# CM6206_PINOUT.net
KiCad netlist of a schematic drawn in Altium Designer
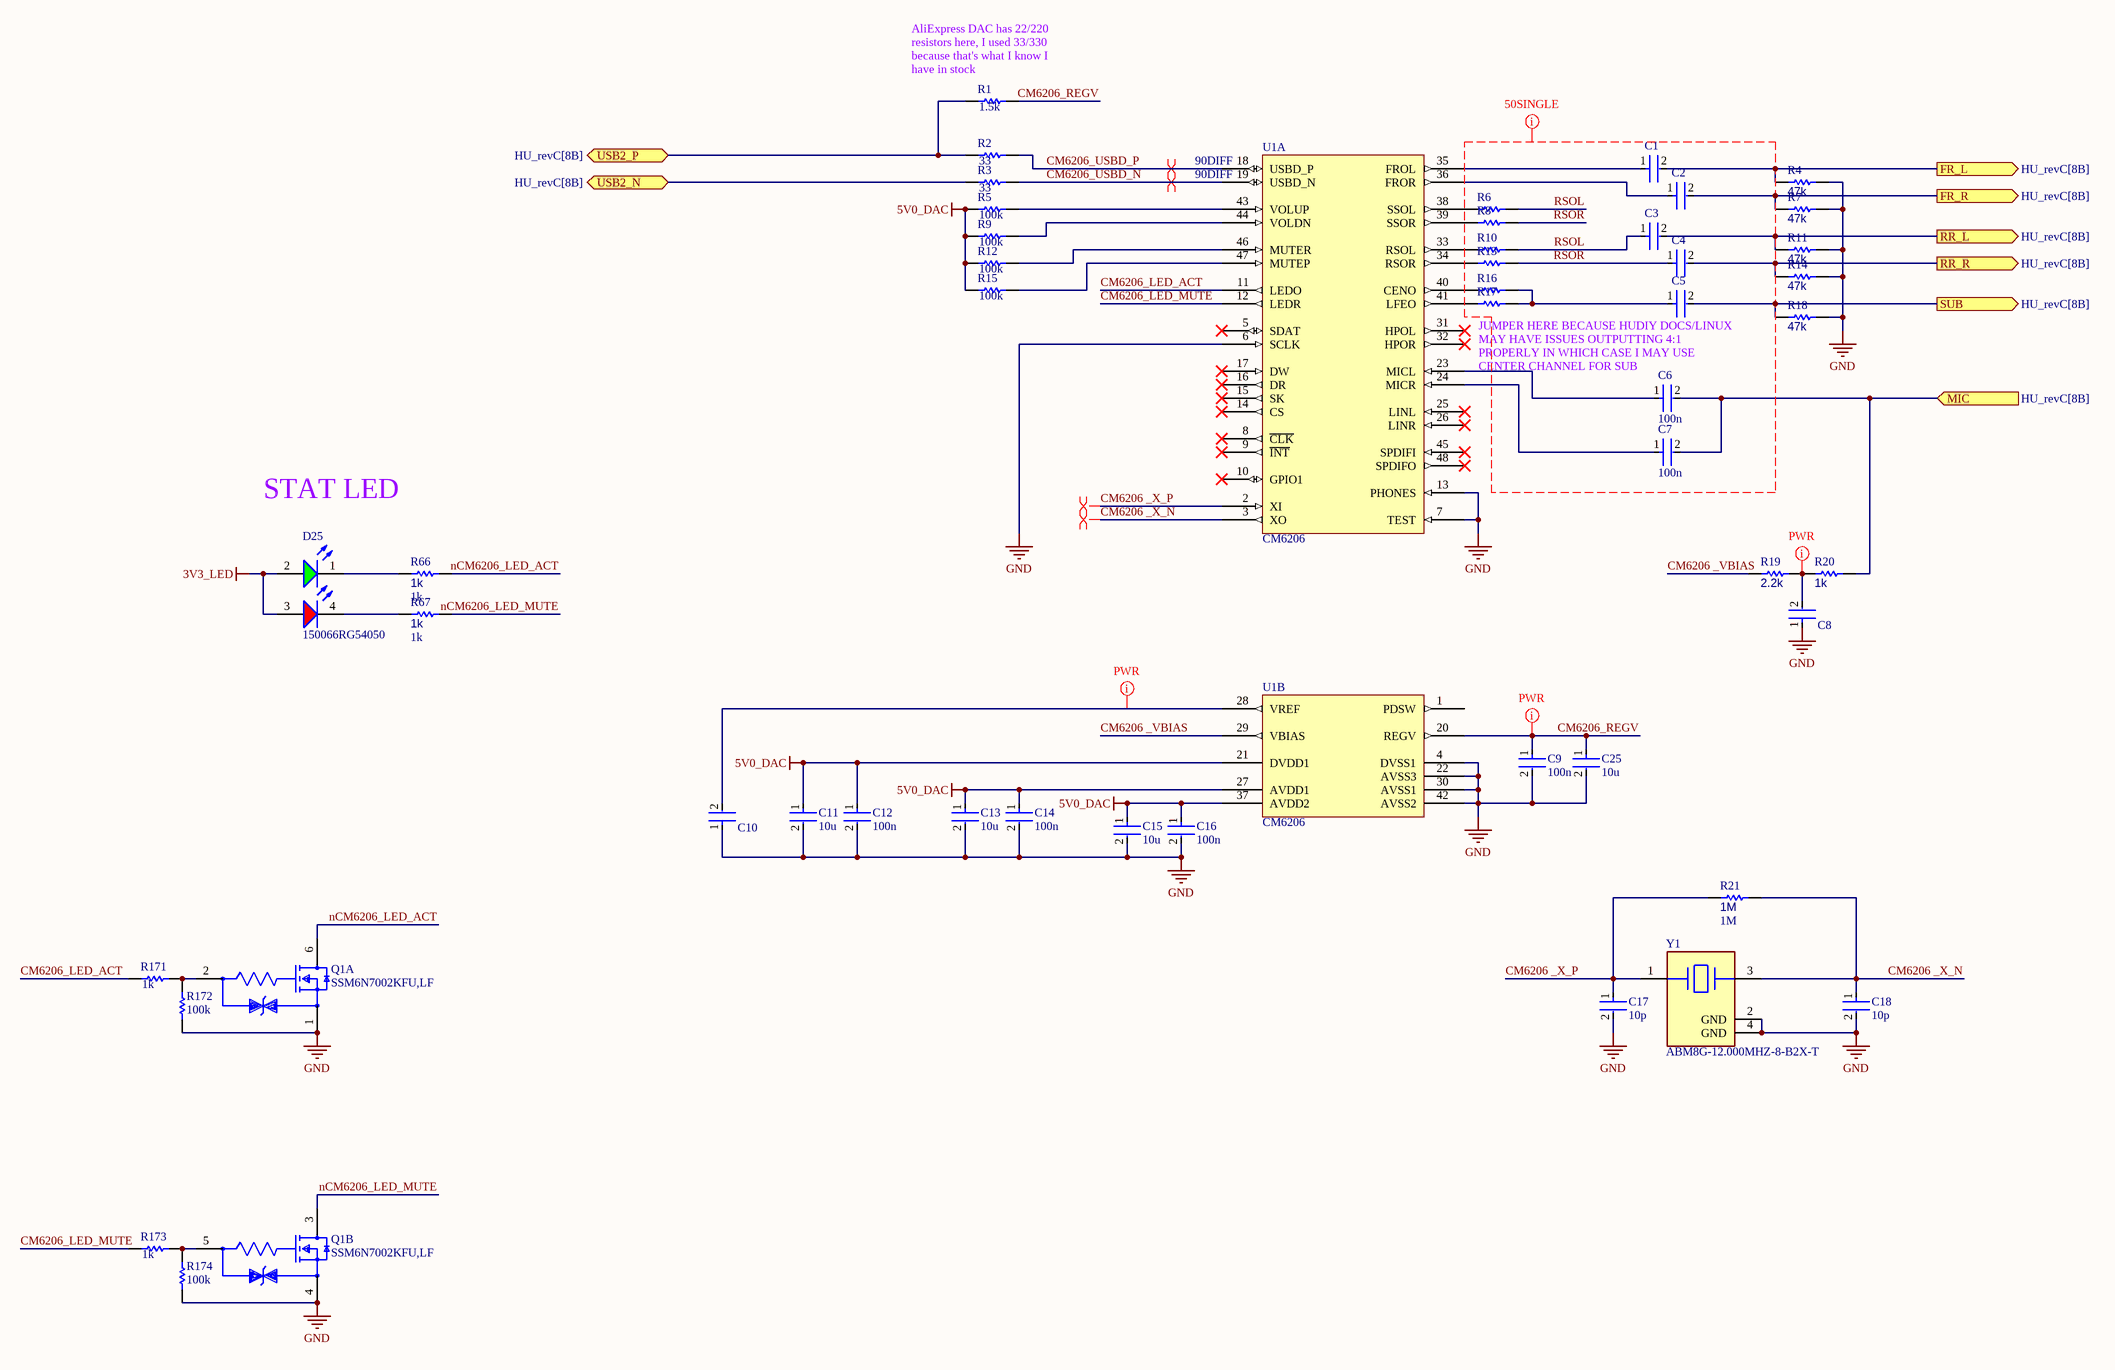
[diagram p0: CM6206_PINOUT.SchDoc]

(export (version "E")
  (design (tool "Eeschema 10.0.6"))
  (components
    (comp (ref "C1")
      (value "EMK107BBJ106MA-T")
      (footprint "FP-0603-L_1_6_0_2-W_0_8_0-MFG")
      (description "Multilayer Ceramic Capacitor 10uF 16V X5R 20% SMD 0603 T/R")
      (fields (field (name "TOLERANCE") "20%"))
      (libsource (lib "Altium Content Vault") (part "b4654b650e69147ec39a6b967a45e02"))
    )
    (comp (ref "C2")
      (value "EMK107BBJ106MA-T")
      (footprint "FP-0603-L_1_6_0_2-W_0_8_0-MFG")
      (description "Multilayer Ceramic Capacitor 10uF 16V X5R 20% SMD 0603 T/R")
      (fields (field (name "TOLERANCE") "20%"))
      (libsource (lib "Altium Content Vault") (part "b4654b650e69147ec39a6b967a45e02"))
    )
    (comp (ref "C3")
      (value "EMK107BBJ106MA-T")
      (footprint "FP-0603-L_1_6_0_2-W_0_8_0-MFG")
      (description "Multilayer Ceramic Capacitor 10uF 16V X5R 20% SMD 0603 T/R")
      (fields (field (name "TOLERANCE") "20%"))
      (libsource (lib "Altium Content Vault") (part "b4654b650e69147ec39a6b967a45e02"))
    )
    (comp (ref "C4")
      (value "EMK107BBJ106MA-T")
      (footprint "FP-0603-L_1_6_0_2-W_0_8_0-MFG")
      (description "Multilayer Ceramic Capacitor 10uF 16V X5R 20% SMD 0603 T/R")
      (fields (field (name "TOLERANCE") "20%"))
      (libsource (lib "Altium Content Vault") (part "b4654b650e69147ec39a6b967a45e02"))
    )
    (comp (ref "C5")
      (value "EMK107BBJ106MA-T")
      (footprint "FP-0603-L_1_6_0_2-W_0_8_0-MFG")
      (description "Multilayer Ceramic Capacitor 10uF 16V X5R 20% SMD 0603 T/R")
      (fields (field (name "TOLERANCE") "20%"))
      (libsource (lib "Altium Content Vault") (part "b4654b650e69147ec39a6b967a45e02"))
    )
    (comp (ref "C6")
      (value "100n")
      (footprint "FP-0402-L_1_0_0_05-W_0_5-IPC_A")
      (description "LARGE PADS, 0402 CAP, CHANGE COMMENT TO MATCH REAL P/N")
      (libsource (lib "Space Concordia") (part "b4654b650e69147ec39a6b967a45e02"))
    )
    (comp (ref "C7")
      (value "100n")
      (footprint "FP-0402-L_1_0_0_05-W_0_5-IPC_A")
      (description "LARGE PADS, 0402 CAP, CHANGE COMMENT TO MATCH REAL P/N")
      (libsource (lib "Space Concordia") (part "b4654b650e69147ec39a6b967a45e02"))
    )
    (comp (ref "C8")
      (value "EMK107BBJ106MA-T")
      (footprint "FP-0603-L_1_6_0_2-W_0_8_0-MFG")
      (description "Multilayer Ceramic Capacitor 10uF 16V X5R 20% SMD 0603 T/R")
      (fields (field (name "TOLERANCE") "20%"))
      (libsource (lib "Altium Content Vault") (part "b4654b650e69147ec39a6b967a45e02"))
    )
    (comp (ref "C9")
      (value "100n")
      (footprint "FP-0402-L_1_0_0_05-W_0_5-IPC_A")
      (description "LARGE PADS, 0402 CAP, CHANGE COMMENT TO MATCH REAL P/N")
      (libsource (lib "Space Concordia") (part "b4654b650e69147ec39a6b967a45e02"))
    )
    (comp (ref "C10")
      (value "EMK107BBJ106MA-T")
      (footprint "FP-0603-L_1_6_0_2-W_0_8_0-MFG")
      (description "Multilayer Ceramic Capacitor 10uF 16V X5R 20% SMD 0603 T/R")
      (fields (field (name "TOLERANCE") "20%"))
      (libsource (lib "Altium Content Vault") (part "b4654b650e69147ec39a6b967a45e02"))
    )
    (comp (ref "C11")
      (value "10u")
      (footprint "FP-0402-L_1_0_0_05-W_0_5-IPC_A")
      (description "LARGE PADS, 0402 CAP, CHANGE COMMENT TO MATCH REAL P/N")
      (libsource (lib "Space Concordia") (part "b4654b650e69147ec39a6b967a45e02"))
    )
    (comp (ref "C12")
      (value "100n")
      (footprint "FP-0402-L_1_0_0_05-W_0_5-IPC_A")
      (description "LARGE PADS, 0402 CAP, CHANGE COMMENT TO MATCH REAL P/N")
      (libsource (lib "Space Concordia") (part "b4654b650e69147ec39a6b967a45e02"))
    )
    (comp (ref "C13")
      (value "10u")
      (footprint "FP-0402-L_1_0_0_05-W_0_5-IPC_A")
      (description "LARGE PADS, 0402 CAP, CHANGE COMMENT TO MATCH REAL P/N")
      (libsource (lib "Space Concordia") (part "b4654b650e69147ec39a6b967a45e02"))
    )
    (comp (ref "C14")
      (value "100n")
      (footprint "FP-0402-L_1_0_0_05-W_0_5-IPC_A")
      (description "LARGE PADS, 0402 CAP, CHANGE COMMENT TO MATCH REAL P/N")
      (libsource (lib "Space Concordia") (part "b4654b650e69147ec39a6b967a45e02"))
    )
    (comp (ref "C15")
      (value "10u")
      (footprint "FP-0402-L_1_0_0_05-W_0_5-IPC_A")
      (description "LARGE PADS, 0402 CAP, CHANGE COMMENT TO MATCH REAL P/N")
      (libsource (lib "Space Concordia") (part "b4654b650e69147ec39a6b967a45e02"))
    )
    (comp (ref "C16")
      (value "100n")
      (footprint "FP-0402-L_1_0_0_05-W_0_5-IPC_A")
      (description "LARGE PADS, 0402 CAP, CHANGE COMMENT TO MATCH REAL P/N")
      (libsource (lib "Space Concordia") (part "b4654b650e69147ec39a6b967a45e02"))
    )
    (comp (ref "C17")
      (value "10p")
      (footprint "FP-0402-L_1_0_0_05-W_0_5-IPC_A")
      (description "LARGE PADS, 0402 CAP, CHANGE COMMENT TO MATCH REAL P/N")
      (libsource (lib "Space Concordia") (part "b4654b650e69147ec39a6b967a45e02"))
    )
    (comp (ref "C18")
      (value "10p")
      (footprint "FP-0402-L_1_0_0_05-W_0_5-IPC_A")
      (description "LARGE PADS, 0402 CAP, CHANGE COMMENT TO MATCH REAL P/N")
      (libsource (lib "Space Concordia") (part "b4654b650e69147ec39a6b967a45e02"))
    )
    (comp (ref "C25")
      (value "10u")
      (footprint "FP-0402-L_1_0_0_05-W_0_5-IPC_A")
      (description "LARGE PADS, 0402 CAP, CHANGE COMMENT TO MATCH REAL P/N")
      (libsource (lib "Space Concordia") (part "b4654b650e69147ec39a6b967a45e02"))
    )
    (comp (ref "D25")
      (value "150066RG54050")
      (footprint "WL-SBCD_0606")
      (description "Led, Red/Grn, 180Mcd/230Mcd, 624Nm/525Nm Rohs Compliant: Yes")
      (fields (field (name "SOURCE") "rgled.SchLib"))
      (libsource (lib "Space Concordia") (part "CMP-004-00034-2"))
    )
    (comp (ref "Q1")
      (value "SSM6N7002KFU,LF")
      (footprint "FP-SSOP6-P-0_65A-MFG")
      (description "Transistor MOSFET Array Dual N-CH 60V 300mA 6-Pin SOT-363 Emboss T/R")
      (libsource (lib "Space Concordia") (part "088aa6ac103fdeebe0d1c52ece6b7b9"))
    )
    (comp (ref "R1")
      (value "1.5k")
      (footprint "R0603B")
      (description "Resistor")
      (libsource (lib "Space Concordia") (part "Resistor"))
    )
    (comp (ref "R2")
      (value "33")
      (footprint "R0603B")
      (description "Resistor")
      (libsource (lib "Space Concordia") (part "Resistor"))
    )
    (comp (ref "R3")
      (value "33")
      (footprint "R0603B")
      (description "Resistor")
      (libsource (lib "Space Concordia") (part "Resistor"))
    )
    (comp (ref "R4")
      (value "47k")
      (footprint "R0603B")
      (description "Resistor")
      (libsource (lib "Space Concordia") (part "Resistor"))
    )
    (comp (ref "R5")
      (value "100k")
      (footprint "R0603B")
      (description "Resistor")
      (libsource (lib "Space Concordia") (part "Resistor"))
    )
    (comp (ref "R6")
      (value "DNP")
      (footprint "RESC1005X40X25ML05T05")
      (description "READ THE NAME")
      (libsource (lib "Space Concordia") (part "CMP-009-00206-2"))
    )
    (comp (ref "R7")
      (value "47k")
      (footprint "R0603B")
      (description "Resistor")
      (libsource (lib "Space Concordia") (part "Resistor"))
    )
    (comp (ref "R8")
      (value "DNP")
      (footprint "RESC1005X40X25ML05T05")
      (description "READ THE NAME")
      (libsource (lib "Space Concordia") (part "CMP-009-00206-2"))
    )
    (comp (ref "R9")
      (value "100k")
      (footprint "R0603B")
      (description "Resistor")
      (libsource (lib "Space Concordia") (part "Resistor"))
    )
    (comp (ref "R10")
      (value "0402 JUMPER")
      (footprint "RESC1005X40X25ML05T05")
      (description "READ THE NAME")
      (libsource (lib "Space Concordia") (part "CMP-009-00206-2"))
    )
    (comp (ref "R11")
      (value "47k")
      (footprint "R0603B")
      (description "Resistor")
      (libsource (lib "Space Concordia") (part "Resistor"))
    )
    (comp (ref "R12")
      (value "100k")
      (footprint "R0603B")
      (description "Resistor")
      (libsource (lib "Space Concordia") (part "Resistor"))
    )
    (comp (ref "R13")
      (value "0402 JUMPER")
      (footprint "RESC1005X40X25ML05T05")
      (description "READ THE NAME")
      (libsource (lib "Space Concordia") (part "CMP-009-00206-2"))
    )
    (comp (ref "R14")
      (value "47k")
      (footprint "R0603B")
      (description "Resistor")
      (libsource (lib "Space Concordia") (part "Resistor"))
    )
    (comp (ref "R15")
      (value "100k")
      (footprint "R0603B")
      (description "Resistor")
      (libsource (lib "Space Concordia") (part "Resistor"))
    )
    (comp (ref "R16")
      (value "DNP")
      (footprint "RESC1005X40X25ML05T05")
      (description "READ THE NAME")
      (libsource (lib "Space Concordia") (part "CMP-009-00206-2"))
    )
    (comp (ref "R17")
      (value "0402 JUMPER")
      (footprint "RESC1005X40X25ML05T05")
      (description "READ THE NAME")
      (libsource (lib "Space Concordia") (part "CMP-009-00206-2"))
    )
    (comp (ref "R18")
      (value "47k")
      (footprint "R0603B")
      (description "Resistor")
      (libsource (lib "Space Concordia") (part "Resistor"))
    )
    (comp (ref "R19")
      (value "2.2k")
      (footprint "R0603B")
      (description "Resistor")
      (libsource (lib "Space Concordia") (part "Resistor"))
    )
    (comp (ref "R20")
      (value "1k")
      (footprint "R0603B")
      (description "Resistor")
      (libsource (lib "Space Concordia") (part "Resistor"))
    )
    (comp (ref "R21")
      (value "1M")
      (footprint "R0603B")
      (description "Resistor")
      (fields (field (name "ALTIUM_VALUE") "1M"))
      (libsource (lib "Space Concordia") (part "Resistor"))
    )
    (comp (ref "R66")
      (value "1k")
      (footprint "R0603B")
      (description "Resistor")
      (fields (field (name "ALTIUM_VALUE") "1k"))
      (libsource (lib "Space Concordia") (part "Resistor"))
    )
    (comp (ref "R67")
      (value "1k")
      (footprint "R0603B")
      (description "Resistor")
      (fields (field (name "ALTIUM_VALUE") "1k"))
      (libsource (lib "Space Concordia") (part "Resistor"))
    )
    (comp (ref "R171")
      (value "1k")
      (footprint "R0603B")
      (description "Resistor")
      (libsource (lib "Space Concordia") (part "Resistor"))
    )
    (comp (ref "R172")
      (value "100k")
      (footprint "R0603B")
      (description "Resistor")
      (libsource (lib "Space Concordia") (part "Resistor"))
    )
    (comp (ref "R173")
      (value "1k")
      (footprint "R0603B")
      (description "Resistor")
      (libsource (lib "Space Concordia") (part "Resistor"))
    )
    (comp (ref "R174")
      (value "100k")
      (footprint "R0603B")
      (description "Resistor")
      (libsource (lib "Space Concordia") (part "Resistor"))
    )
    (comp (ref "U1")
      (value "CM6206")
      (footprint "CQFP50P900X900X160-48N")
      (description "Highly Integrated USB Audio I/O Controller")
      (libsource (lib "Space Concordia") (part "CM6206"))
    )
    (comp (ref "Y1")
      (value "ABM8G-12.000MHZ-8-B2X-T")
      (footprint "FP-ABM8G-MFG")
      (description "Crystal 12MHz ±20ppm (Tol) ±20ppm (Stability) 8pF FUND 120Ω 4-Pin SMD T/R")
      (libsource (lib "Altium Content Vault") (part "48e526d86b7f2615d98721063c72f49"))
    )
  )
  (nets
    (net (code "1") (name "/CM6206 _VBIAS") (class "Default")
      (node (ref "R19") (pin "2") (pinfunction "2_2") (pintype "passive"))
      (node (ref "U1") (pin "29") (pinfunction "VBIAS_29") (pintype "output"))
    )
    (net (code "2") (name "/CM6206 _X_N") (class "Default")
      (node (ref "C18") (pin "1") (pinfunction "1_1") (pintype "passive"))
      (node (ref "R21") (pin "1") (pinfunction "1_1") (pintype "passive"))
      (node (ref "U1") (pin "3") (pinfunction "XO_3") (pintype "output"))
      (node (ref "Y1") (pin "3") (pinfunction "3_3") (pintype "passive"))
    )
    (net (code "3") (name "/CM6206 _X_P") (class "Default")
      (node (ref "C17") (pin "1") (pinfunction "1_1") (pintype "passive"))
      (node (ref "R21") (pin "2") (pinfunction "2_2") (pintype "passive"))
      (node (ref "U1") (pin "2") (pinfunction "XI_2") (pintype "input"))
      (node (ref "Y1") (pin "1") (pinfunction "1_1") (pintype "passive"))
    )
    (net (code "4") (name "/CM6206_LED_ACT") (class "Default")
      (node (ref "R171") (pin "2") (pinfunction "2_2") (pintype "passive"))
      (node (ref "U1") (pin "11") (pinfunction "LEDO_11") (pintype "output"))
    )
    (net (code "5") (name "/CM6206_LED_MUTE") (class "Default")
      (node (ref "R173") (pin "2") (pinfunction "2_2") (pintype "passive"))
      (node (ref "U1") (pin "12") (pinfunction "LEDR_12") (pintype "output"))
    )
    (net (code "6") (name "/CM6206_REGV") (class "Default")
      (node (ref "C25") (pin "1") (pinfunction "1_1") (pintype "passive"))
      (node (ref "C9") (pin "1") (pinfunction "1_1") (pintype "passive"))
      (node (ref "R1") (pin "1") (pinfunction "1_1") (pintype "passive"))
      (node (ref "U1") (pin "20") (pinfunction "REGV_20") (pintype "output"))
    )
    (net (code "7") (name "/CM6206_USBD_N") (class "Default")
      (node (ref "R3") (pin "1") (pinfunction "1_1") (pintype "passive"))
      (node (ref "U1") (pin "19") (pinfunction "USBD_N_19") (pintype "bidirectional"))
    )
    (net (code "8") (name "/CM6206_USBD_P") (class "Default")
      (node (ref "R2") (pin "1") (pinfunction "1_1") (pintype "passive"))
      (node (ref "U1") (pin "18") (pinfunction "USBD_P_18") (pintype "bidirectional"))
    )
    (net (code "9") (name "/FR_L") (class "Default")
      (node (ref "C1") (pin "2") (pinfunction "2_2") (pintype "passive"))
      (node (ref "R4") (pin "2") (pinfunction "2_2") (pintype "passive"))
    )
    (net (code "10") (name "/FR_R") (class "Default")
      (node (ref "C2") (pin "2") (pinfunction "2_2") (pintype "passive"))
      (node (ref "R7") (pin "2") (pinfunction "2_2") (pintype "passive"))
    )
    (net (code "11") (name "/MIC") (class "Default")
      (node (ref "C6") (pin "2") (pinfunction "2_2") (pintype "passive"))
      (node (ref "C7") (pin "2") (pinfunction "2_2") (pintype "passive"))
      (node (ref "R20") (pin "1") (pinfunction "1_1") (pintype "passive"))
    )
    (net (code "12") (name "/RR_L") (class "Default")
      (node (ref "C3") (pin "2") (pinfunction "2_2") (pintype "passive"))
      (node (ref "R11") (pin "2") (pinfunction "2_2") (pintype "passive"))
    )
    (net (code "13") (name "/RR_R") (class "Default")
      (node (ref "C4") (pin "2") (pinfunction "2_2") (pintype "passive"))
      (node (ref "R14") (pin "2") (pinfunction "2_2") (pintype "passive"))
    )
    (net (code "14") (name "/RSOL") (class "Default")
      (node (ref "C3") (pin "1") (pinfunction "1_1") (pintype "passive"))
      (node (ref "R10") (pin "2") (pinfunction "2_2") (pintype "passive"))
      (node (ref "R6") (pin "2") (pinfunction "2_2") (pintype "passive"))
    )
    (net (code "15") (name "/RSOR") (class "Default")
      (node (ref "C4") (pin "1") (pinfunction "1_1") (pintype "passive"))
      (node (ref "R13") (pin "2") (pinfunction "2_2") (pintype "passive"))
      (node (ref "R8") (pin "2") (pinfunction "2_2") (pintype "passive"))
    )
    (net (code "16") (name "/SUB") (class "Default")
      (node (ref "C5") (pin "2") (pinfunction "2_2") (pintype "passive"))
      (node (ref "R18") (pin "2") (pinfunction "2_2") (pintype "passive"))
    )
    (net (code "17") (name "/USB2_N") (class "Default")
      (node (ref "R3") (pin "2") (pinfunction "2_2") (pintype "passive"))
    )
    (net (code "18") (name "/USB2_P") (class "Default")
      (node (ref "R1") (pin "2") (pinfunction "2_2") (pintype "passive"))
      (node (ref "R2") (pin "2") (pinfunction "2_2") (pintype "passive"))
    )
    (net (code "19") (name "/nCM6206_LED_ACT") (class "Default")
      (node (ref "Q1") (pin "6") (pinfunction "Drain1_6") (pintype "passive"))
      (node (ref "R66") (pin "2") (pinfunction "2_2") (pintype "passive"))
    )
    (net (code "20") (name "/nCM6206_LED_MUTE") (class "Default")
      (node (ref "Q1") (pin "3") (pinfunction "Drain2_3") (pintype "passive"))
      (node (ref "R67") (pin "2") (pinfunction "2_2") (pintype "passive"))
    )
    (net (code "21") (name "3V3_LED") (class "Default")
      (node (ref "D25") (pin "2") (pinfunction "A_2") (pintype "passive"))
      (node (ref "D25") (pin "3") (pinfunction "A_3") (pintype "passive"))
    )
    (net (code "22") (name "5V0_DAC") (class "Default")
      (node (ref "C11") (pin "1") (pinfunction "1_1") (pintype "passive"))
      (node (ref "C12") (pin "1") (pinfunction "1_1") (pintype "passive"))
      (node (ref "C13") (pin "1") (pinfunction "1_1") (pintype "passive"))
      (node (ref "C14") (pin "1") (pinfunction "1_1") (pintype "passive"))
      (node (ref "C15") (pin "1") (pinfunction "1_1") (pintype "passive"))
      (node (ref "C16") (pin "1") (pinfunction "1_1") (pintype "passive"))
      (node (ref "R12") (pin "2") (pinfunction "2_2") (pintype "passive"))
      (node (ref "R15") (pin "2") (pinfunction "2_2") (pintype "passive"))
      (node (ref "R5") (pin "2") (pinfunction "2_2") (pintype "passive"))
      (node (ref "R9") (pin "2") (pinfunction "2_2") (pintype "passive"))
      (node (ref "U1") (pin "21") (pinfunction "DVDD1_21") (pintype "power_in"))
      (node (ref "U1") (pin "27") (pinfunction "AVDD1_27") (pintype "power_in"))
      (node (ref "U1") (pin "37") (pinfunction "AVDD2_37") (pintype "power_in"))
    )
    (net (code "23") (name "GND") (class "Default")
      (node (ref "C10") (pin "1") (pinfunction "1_1") (pintype "passive"))
      (node (ref "C11") (pin "2") (pinfunction "2_2") (pintype "passive"))
      (node (ref "C12") (pin "2") (pinfunction "2_2") (pintype "passive"))
      (node (ref "C13") (pin "2") (pinfunction "2_2") (pintype "passive"))
      (node (ref "C14") (pin "2") (pinfunction "2_2") (pintype "passive"))
      (node (ref "C15") (pin "2") (pinfunction "2_2") (pintype "passive"))
      (node (ref "C16") (pin "2") (pinfunction "2_2") (pintype "passive"))
      (node (ref "C17") (pin "2") (pinfunction "2_2") (pintype "passive"))
      (node (ref "C18") (pin "2") (pinfunction "2_2") (pintype "passive"))
      (node (ref "C25") (pin "2") (pinfunction "2_2") (pintype "passive"))
      (node (ref "C8") (pin "1") (pinfunction "1_1") (pintype "passive"))
      (node (ref "C9") (pin "2") (pinfunction "2_2") (pintype "passive"))
      (node (ref "Q1") (pin "1") (pinfunction "Source1_1") (pintype "passive"))
      (node (ref "Q1") (pin "4") (pinfunction "Source2_4") (pintype "passive"))
      (node (ref "R11") (pin "1") (pinfunction "1_1") (pintype "passive"))
      (node (ref "R14") (pin "1") (pinfunction "1_1") (pintype "passive"))
      (node (ref "R172") (pin "2") (pinfunction "2_2") (pintype "passive"))
      (node (ref "R174") (pin "2") (pinfunction "2_2") (pintype "passive"))
      (node (ref "R18") (pin "1") (pinfunction "1_1") (pintype "passive"))
      (node (ref "R4") (pin "1") (pinfunction "1_1") (pintype "passive"))
      (node (ref "R7") (pin "1") (pinfunction "1_1") (pintype "passive"))
      (node (ref "U1") (pin "13") (pinfunction "PHONES_13") (pintype "input"))
      (node (ref "U1") (pin "22") (pinfunction "AVSS3_22") (pintype "power_in"))
      (node (ref "U1") (pin "30") (pinfunction "AVSS1_30") (pintype "power_in"))
      (node (ref "U1") (pin "4") (pinfunction "DVSS1_4") (pintype "power_in"))
      (node (ref "U1") (pin "42") (pinfunction "AVSS2_42") (pintype "power_in"))
      (node (ref "U1") (pin "6") (pinfunction "SCLK_6") (pintype "input"))
      (node (ref "U1") (pin "7") (pinfunction "TEST_7") (pintype "input"))
      (node (ref "Y1") (pin "2") (pinfunction "GND_2") (pintype "power_in"))
      (node (ref "Y1") (pin "4") (pinfunction "GND_4") (pintype "power_in"))
    )
    (net (code "24") (name "Net-(C5-Pad1)") (class "Default")
      (node (ref "C5") (pin "1") (pinfunction "1_1") (pintype "passive"))
      (node (ref "R16") (pin "2") (pinfunction "2_2") (pintype "passive"))
      (node (ref "R17") (pin "2") (pinfunction "2_2") (pintype "passive"))
    )
    (net (code "25") (name "Net-(C8-Pad2)") (class "Default")
      (node (ref "C8") (pin "2") (pinfunction "2_2") (pintype "passive"))
      (node (ref "R19") (pin "1") (pinfunction "1_1") (pintype "passive"))
      (node (ref "R20") (pin "2") (pinfunction "2_2") (pintype "passive"))
    )
    (net (code "26") (name "Net-(D25-K-Pad1)") (class "Default")
      (node (ref "D25") (pin "1") (pinfunction "K_1") (pintype "passive"))
      (node (ref "R66") (pin "1") (pinfunction "1_1") (pintype "passive"))
    )
    (net (code "27") (name "Net-(D25-K-Pad4)") (class "Default")
      (node (ref "D25") (pin "4") (pinfunction "K_4") (pintype "passive"))
      (node (ref "R67") (pin "1") (pinfunction "1_1") (pintype "passive"))
    )
    (net (code "28") (name "Net-(Q1A-Gate1)") (class "Default")
      (node (ref "Q1") (pin "2") (pinfunction "Gate1_2") (pintype "passive"))
      (node (ref "R171") (pin "1") (pinfunction "1_1") (pintype "passive"))
      (node (ref "R172") (pin "1") (pinfunction "1_1") (pintype "passive"))
    )
    (net (code "29") (name "Net-(Q1B-Gate2)") (class "Default")
      (node (ref "Q1") (pin "5") (pinfunction "Gate2_5") (pintype "passive"))
      (node (ref "R173") (pin "1") (pinfunction "1_1") (pintype "passive"))
      (node (ref "R174") (pin "1") (pinfunction "1_1") (pintype "passive"))
    )
    (net (code "30") (name "Net-(U1A-CENO)") (class "Default")
      (node (ref "R16") (pin "1") (pinfunction "1_1") (pintype "passive"))
      (node (ref "U1") (pin "40") (pinfunction "CENO_40") (pintype "output"))
    )
    (net (code "31") (name "Net-(U1A-FROL)") (class "Default")
      (node (ref "C1") (pin "1") (pinfunction "1_1") (pintype "passive"))
      (node (ref "U1") (pin "35") (pinfunction "FROL_35") (pintype "output"))
    )
    (net (code "32") (name "Net-(U1A-FROR)") (class "Default")
      (node (ref "C2") (pin "1") (pinfunction "1_1") (pintype "passive"))
      (node (ref "U1") (pin "36") (pinfunction "FROR_36") (pintype "output"))
    )
    (net (code "33") (name "Net-(U1A-LFEO)") (class "Default")
      (node (ref "R17") (pin "1") (pinfunction "1_1") (pintype "passive"))
      (node (ref "U1") (pin "41") (pinfunction "LFEO_41") (pintype "output"))
    )
    (net (code "34") (name "Net-(U1A-MICL)") (class "Default")
      (node (ref "C6") (pin "1") (pinfunction "1_1") (pintype "passive"))
      (node (ref "U1") (pin "23") (pinfunction "MICL_23") (pintype "input"))
    )
    (net (code "35") (name "Net-(U1A-MICR)") (class "Default")
      (node (ref "C7") (pin "1") (pinfunction "1_1") (pintype "passive"))
      (node (ref "U1") (pin "24") (pinfunction "MICR_24") (pintype "input"))
    )
    (net (code "36") (name "Net-(U1A-MUTEP)") (class "Default")
      (node (ref "R15") (pin "1") (pinfunction "1_1") (pintype "passive"))
      (node (ref "U1") (pin "47") (pinfunction "MUTEP_47") (pintype "input"))
    )
    (net (code "37") (name "Net-(U1A-MUTER)") (class "Default")
      (node (ref "R12") (pin "1") (pinfunction "1_1") (pintype "passive"))
      (node (ref "U1") (pin "46") (pinfunction "MUTER_46") (pintype "input"))
    )
    (net (code "38") (name "Net-(U1A-RSOL)") (class "Default")
      (node (ref "R10") (pin "1") (pinfunction "1_1") (pintype "passive"))
      (node (ref "U1") (pin "33") (pinfunction "RSOL_33") (pintype "output"))
    )
    (net (code "39") (name "Net-(U1A-RSOR)") (class "Default")
      (node (ref "R13") (pin "1") (pinfunction "1_1") (pintype "passive"))
      (node (ref "U1") (pin "34") (pinfunction "RSOR_34") (pintype "output"))
    )
    (net (code "40") (name "Net-(U1A-SSOL)") (class "Default")
      (node (ref "R6") (pin "1") (pinfunction "1_1") (pintype "passive"))
      (node (ref "U1") (pin "38") (pinfunction "SSOL_38") (pintype "output"))
    )
    (net (code "41") (name "Net-(U1A-SSOR)") (class "Default")
      (node (ref "R8") (pin "1") (pinfunction "1_1") (pintype "passive"))
      (node (ref "U1") (pin "39") (pinfunction "SSOR_39") (pintype "output"))
    )
    (net (code "42") (name "Net-(U1A-VOLDN)") (class "Default")
      (node (ref "R9") (pin "1") (pinfunction "1_1") (pintype "passive"))
      (node (ref "U1") (pin "44") (pinfunction "VOLDN_44") (pintype "input"))
    )
    (net (code "43") (name "Net-(U1A-VOLUP)") (class "Default")
      (node (ref "R5") (pin "1") (pinfunction "1_1") (pintype "passive"))
      (node (ref "U1") (pin "43") (pinfunction "VOLUP_43") (pintype "input"))
    )
    (net (code "44") (name "Net-(U1B-VREF)") (class "Default")
      (node (ref "C10") (pin "2") (pinfunction "2_2") (pintype "passive"))
      (node (ref "U1") (pin "28") (pinfunction "VREF_28") (pintype "output"))
    )
    (net (code "45") (name "unconnected-(U1A-CS-Pad14)") (class "Default")
      (node (ref "U1") (pin "14") (pinfunction "CS_14") (pintype "output+no_connect"))
    )
    (net (code "46") (name "unconnected-(U1A-DR-Pad16)") (class "Default")
      (node (ref "U1") (pin "16") (pinfunction "DR_16") (pintype "output+no_connect"))
    )
    (net (code "47") (name "unconnected-(U1A-DW-Pad17)") (class "Default")
      (node (ref "U1") (pin "17") (pinfunction "DW_17") (pintype "input+no_connect"))
    )
    (net (code "48") (name "unconnected-(U1A-GPIO1-Pad10)") (class "Default")
      (node (ref "U1") (pin "10") (pinfunction "GPIO1_10") (pintype "bidirectional+no_connect"))
    )
    (net (code "49") (name "unconnected-(U1A-HPOL-Pad31)") (class "Default")
      (node (ref "U1") (pin "31") (pinfunction "HPOL_31") (pintype "output+no_connect"))
    )
    (net (code "50") (name "unconnected-(U1A-HPOR-Pad32)") (class "Default")
      (node (ref "U1") (pin "32") (pinfunction "HPOR_32") (pintype "output+no_connect"))
    )
    (net (code "51") (name "unconnected-(U1A-LINL-Pad25)") (class "Default")
      (node (ref "U1") (pin "25") (pinfunction "LINL_25") (pintype "input+no_connect"))
    )
    (net (code "52") (name "unconnected-(U1A-LINR-Pad26)") (class "Default")
      (node (ref "U1") (pin "26") (pinfunction "LINR_26") (pintype "input+no_connect"))
    )
    (net (code "53") (name "unconnected-(U1A-SDAT-Pad5)") (class "Default")
      (node (ref "U1") (pin "5") (pinfunction "SDAT_5") (pintype "bidirectional+no_connect"))
    )
    (net (code "54") (name "unconnected-(U1A-SK-Pad15)") (class "Default")
      (node (ref "U1") (pin "15") (pinfunction "SK_15") (pintype "output+no_connect"))
    )
    (net (code "55") (name "unconnected-(U1A-SPDIFI-Pad45)") (class "Default")
      (node (ref "U1") (pin "45") (pinfunction "SPDIFI_45") (pintype "input+no_connect"))
    )
    (net (code "56") (name "unconnected-(U1A-SPDIFO-Pad48)") (class "Default")
      (node (ref "U1") (pin "48") (pinfunction "SPDIFO_48") (pintype "output+no_connect"))
    )
    (net (code "57") (name "unconnected-(U1A-~{CLK}-Pad8)") (class "Default")
      (node (ref "U1") (pin "8") (pinfunction "~{CLK}_8") (pintype "output+no_connect"))
    )
    (net (code "58") (name "unconnected-(U1A-~{INT}-Pad9)") (class "Default")
      (node (ref "U1") (pin "9") (pinfunction "~{INT}_9") (pintype "output+no_connect"))
    )
    (net (code "59") (name "unconnected-(U1B-PDSW-Pad1)") (class "Default")
      (node (ref "U1") (pin "1") (pinfunction "PDSW_1") (pintype "output"))
    )
  )
)
